# EPS_3V3_EMI-Filter_In.net
KiCad netlist of a schematic drawn in Altium Designer
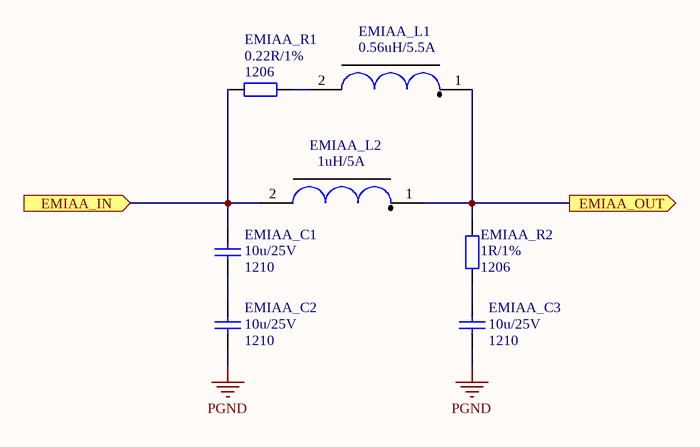
[diagram p0: EPS_3V3_EMI-Filter_In.SchDoc]

(export (version "E")
  (design (tool "Eeschema 10.0.6"))
  (components
    (comp (ref "EMIAA_C1")
      (value "10u/25V")
      (footprint "SMD_Capacitor_1210")
      (description "Ceramic Cap Murata Automotive 10u/25V X7R 1210")
      (fields
        (field (name "MANUFACTURER") "Murata")
        (field (name "MANUFACTURERPARTNUMBER") "GCJ32ER71E106KA12L")
        (field (name "PACKAGE") "1210")
      )
      (libsource (lib "capacitors") (part "Cer_GCJ32ER71E106KA12L"))
    )
    (comp (ref "EMIAA_C2")
      (value "10u/25V")
      (footprint "SMD_Capacitor_1210")
      (description "Ceramic Cap Murata Automotive 10u/25V X7R 1210")
      (fields
        (field (name "MANUFACTURER") "Murata")
        (field (name "MANUFACTURERPARTNUMBER") "GCJ32ER71E106KA12L")
        (field (name "PACKAGE") "1210")
      )
      (libsource (lib "capacitors") (part "Cer_GCJ32ER71E106KA12L"))
    )
    (comp (ref "EMIAA_C3")
      (value "10u/25V")
      (footprint "SMD_Capacitor_1210")
      (description "Ceramic Cap Murata Automotive 10u/25V X7R 1210")
      (fields
        (field (name "MANUFACTURER") "Murata")
        (field (name "MANUFACTURERPARTNUMBER") "GCJ32ER71E106KA12L")
        (field (name "PACKAGE") "1210")
      )
      (libsource (lib "capacitors") (part "Cer_GCJ32ER71E106KA12L"))
    )
    (comp (ref "EMIAA_L1")
      (value "0.56uH/5.5A")
      (footprint "Vishay_IHLP1212")
      (description "Vishay IHLP1212 Inductor, L=0.56uH, Irise40deg=5.5A, ESR=16mR, SRF=1MHz.")
      (fields
        (field (name "MANUFACTURER") "Vishay")
        (field (name "MANUFACTURERPARTNUMBER") "IHLP1212BZERR56M11")
      )
      (libsource (lib "inductors") (part "IHLP1212BZERR56M11"))
    )
    (comp (ref "EMIAA_L2")
      (value "1uH/5A")
      (footprint "Vishay_IHLP1212")
      (description "Vishay IHLP1212 Inductor, L=1uH, Irise40deg=5A, ESR=20mR, SRF=1MHz.")
      (fields
        (field (name "MANUFACTURER") "Vishay")
        (field (name "MANUFACTURERPARTNUMBER") "IHLP1212BZER1R0M11")
      )
      (libsource (lib "inductors") (part "IHLP1212BZER1R0M11"))
    )
    (comp (ref "EMIAA_R1")
      (value "0.22R/1%")
      (footprint "SMD_Resistor_1206")
      (description "Panasonic Resistor 0.22R 1% 1206 330mW")
      (fields
        (field (name "MANUFACTURER") "Panasonic")
        (field (name "MANUFACTURERPARTNUMBER") "ERJ-8BQFR22V")
        (field (name "PACKAGE") "1206")
      )
      (libsource (lib "resistors") (part "ERJ-8BQFR22V"))
    )
    (comp (ref "EMIAA_R2")
      (value "1R/1%")
      (footprint "SMD_Resistor_1206")
      (description "Panasonic Resistor 1R 1% 1206 330mW")
      (fields
        (field (name "MANUFACTURERPARTNUMBER") "ERJ-8BQF1R0V")
        (field (name "MANUFACTURER") "Panasonic")
        (field (name "PACKAGE") "1206")
      )
      (libsource (lib "resistors") (part "ERJ-8BQF1R0V"))
    )
  )
  (nets
    (net (code "1") (name "/EMIAA_IN") (class "Default")
      (node (ref "EMIAA_C1") (pin "1") (pinfunction "1_1") (pintype "passive"))
      (node (ref "EMIAA_L2") (pin "2") (pinfunction "2_2") (pintype "passive"))
      (node (ref "EMIAA_R1") (pin "1") (pinfunction "1_1") (pintype "passive"))
    )
    (net (code "2") (name "/EMIAA_OUT") (class "Default")
      (node (ref "EMIAA_L1") (pin "1") (pinfunction "1_1") (pintype "passive"))
      (node (ref "EMIAA_L2") (pin "1") (pinfunction "1_1") (pintype "passive"))
      (node (ref "EMIAA_R2") (pin "2") (pinfunction "2_2") (pintype "passive"))
    )
    (net (code "3") (name "Net-(EMIAA_C1-Pad2)") (class "Default")
      (node (ref "EMIAA_C1") (pin "2") (pinfunction "2_2") (pintype "passive"))
      (node (ref "EMIAA_C2") (pin "1") (pinfunction "1_1") (pintype "passive"))
    )
    (net (code "4") (name "Net-(EMIAA_C3-Pad1)") (class "Default")
      (node (ref "EMIAA_C3") (pin "1") (pinfunction "1_1") (pintype "passive"))
      (node (ref "EMIAA_R2") (pin "1") (pinfunction "1_1") (pintype "passive"))
    )
    (net (code "5") (name "Net-(EMIAA_L1-Pad2)") (class "Default")
      (node (ref "EMIAA_L1") (pin "2") (pinfunction "2_2") (pintype "passive"))
      (node (ref "EMIAA_R1") (pin "2") (pinfunction "2_2") (pintype "passive"))
    )
    (net (code "6") (name "PGND") (class "Default")
      (node (ref "EMIAA_C2") (pin "2") (pinfunction "2_2") (pintype "passive"))
      (node (ref "EMIAA_C3") (pin "2") (pinfunction "2_2") (pintype "passive"))
    )
  )
)
